# stepper-hbridge-xiao.net
KiCad netlist of a schematic drawn in EAGLE
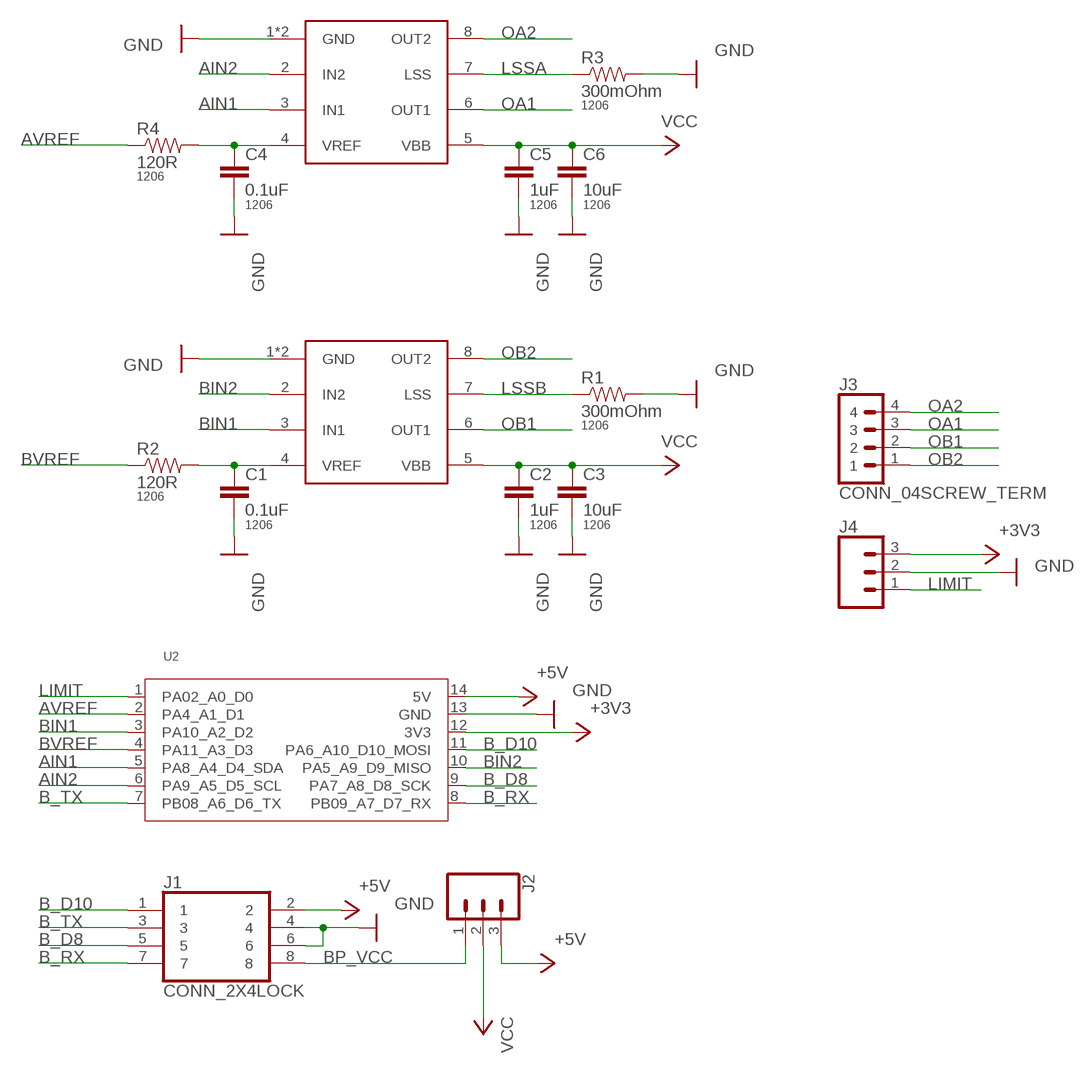
[diagram p0: schematic, sheet 1]

(export (version "E")
  (design (tool "Eeschema 10.0.6"))
  (components
    (comp (ref "C1")
      (value "0.1uF")
      (footprint "eagle-import:1206")
      (fields (field (name "PACKAGE") "1206"))
      (libsource (lib "eagle-import") (part "CAP1206"))
    )
    (comp (ref "C2")
      (value "1uF")
      (footprint "eagle-import:1206")
      (fields (field (name "PACKAGE") "1206"))
      (libsource (lib "eagle-import") (part "CAP1206"))
    )
    (comp (ref "C3")
      (value "10uF")
      (footprint "eagle-import:1206")
      (fields (field (name "PACKAGE") "1206"))
      (libsource (lib "eagle-import") (part "CAP1206"))
    )
    (comp (ref "C4")
      (value "0.1uF")
      (footprint "eagle-import:1206")
      (fields (field (name "PACKAGE") "1206"))
      (libsource (lib "eagle-import") (part "CAP1206"))
    )
    (comp (ref "C5")
      (value "1uF")
      (footprint "eagle-import:1206")
      (fields (field (name "PACKAGE") "1206"))
      (libsource (lib "eagle-import") (part "CAP1206"))
    )
    (comp (ref "C6")
      (value "10uF")
      (footprint "eagle-import:1206")
      (fields (field (name "PACKAGE") "1206"))
      (libsource (lib "eagle-import") (part "CAP1206"))
    )
    (comp (ref "J1")
      (value "CONN_2X4LOCK")
      (footprint "eagle-import:2X4-LOCK")
      (libsource (lib "eagle-import") (part "CONN_2X4LOCK"))
    )
    (comp (ref "J2")
      (value "CONN_03LOCK_NO_SILK")
      (footprint "eagle-import:1X03_LOCK_NO_SILK")
      (libsource (lib "eagle-import") (part "CONN_03LOCK_NO_SILK"))
    )
    (comp (ref "J3")
      (value "CONN_04SCREW_TERM")
      (footprint "eagle-import:1X04_SCREW-TERM")
      (libsource (lib "eagle-import") (part "CONN_04SCREW_TERM"))
    )
    (comp (ref "J4")
      (value "CONN_03LOCK_NO_SILK")
      (footprint "eagle-import:1X03_LOCK_NO_SILK")
      (libsource (lib "eagle-import") (part "CONN_03LOCK_NO_SILK"))
    )
    (comp (ref "R1")
      (value "300mOhm")
      (footprint "eagle-import:1206")
      (fields (field (name "PACKAGE") "1206"))
      (libsource (lib "eagle-import") (part "RESISTOR1206"))
    )
    (comp (ref "R2")
      (value "120R")
      (footprint "eagle-import:1206")
      (fields (field (name "PACKAGE") "1206"))
      (libsource (lib "eagle-import") (part "RESISTOR1206"))
    )
    (comp (ref "R3")
      (value "300mOhm")
      (footprint "eagle-import:1206")
      (fields (field (name "PACKAGE") "1206"))
      (libsource (lib "eagle-import") (part "RESISTOR1206"))
    )
    (comp (ref "R4")
      (value "120R")
      (footprint "eagle-import:1206")
      (fields (field (name "PACKAGE") "1206"))
      (libsource (lib "eagle-import") (part "RESISTOR1206"))
    )
    (comp (ref "U1")
      (value "A4950")
      (footprint "eagle-import:SOIC8_PAD")
      (libsource (lib "eagle-import") (part "A4950"))
    )
    (comp (ref "U2")
      (value "MOUDLE-SEEEDUINO-XIAO-DIP")
      (footprint "eagle-import:MOUDLE14P-2.54-21X17.8MM")
      (libsource (lib "eagle-import") (part "MOUDLE-SEEEDUINO-XIAO-DIP"))
    )
    (comp (ref "U3")
      (value "A4950")
      (footprint "eagle-import:SOIC8_PAD")
      (libsource (lib "eagle-import") (part "A4950"))
    )
  )
  (nets
    (net (code "1") (name "+3V3") (class "Default")
      (node (ref "J4") (pin "3") (pinfunction "3_3") (pintype "passive"))
      (node (ref "U2") (pin "12") (pinfunction "3V3_12") (pintype "bidirectional"))
    )
    (net (code "2") (name "+5V") (class "Default")
      (node (ref "J1") (pin "2") (pinfunction "2_2") (pintype "passive"))
      (node (ref "J2") (pin "3") (pinfunction "3_3") (pintype "passive"))
      (node (ref "U2") (pin "14") (pinfunction "5V_14") (pintype "bidirectional"))
    )
    (net (code "3") (name "/AIN1") (class "Default")
      (node (ref "U2") (pin "5") (pinfunction "PA8_A4_D4_SDA_5") (pintype "bidirectional"))
      (node (ref "U3") (pin "3") (pinfunction "IN1_3") (pintype "bidirectional"))
    )
    (net (code "4") (name "/AIN2") (class "Default")
      (node (ref "U2") (pin "6") (pinfunction "PA9_A5_D5_SCL_6") (pintype "bidirectional"))
      (node (ref "U3") (pin "2") (pinfunction "IN2_2") (pintype "bidirectional"))
    )
    (net (code "5") (name "/AVREF") (class "Default")
      (node (ref "R4") (pin "1") (pinfunction "1_1") (pintype "passive"))
      (node (ref "U2") (pin "2") (pinfunction "PA4_A1_D1_2") (pintype "bidirectional"))
    )
    (net (code "6") (name "/BIN1") (class "Default")
      (node (ref "U1") (pin "3") (pinfunction "IN1_3") (pintype "bidirectional"))
      (node (ref "U2") (pin "3") (pinfunction "PA10_A2_D2_3") (pintype "bidirectional"))
    )
    (net (code "7") (name "/BIN2") (class "Default")
      (node (ref "U1") (pin "2") (pinfunction "IN2_2") (pintype "bidirectional"))
      (node (ref "U2") (pin "10") (pinfunction "PA5_A9_D9_MISO_10") (pintype "bidirectional"))
    )
    (net (code "8") (name "/BP_VCC") (class "Default")
      (node (ref "J1") (pin "8") (pinfunction "8_8") (pintype "passive"))
      (node (ref "J2") (pin "1") (pinfunction "1_1") (pintype "passive"))
    )
    (net (code "9") (name "/BVREF") (class "Default")
      (node (ref "R2") (pin "1") (pinfunction "1_1") (pintype "passive"))
      (node (ref "U2") (pin "4") (pinfunction "PA11_A3_D3_4") (pintype "bidirectional"))
    )
    (net (code "10") (name "/B_D8") (class "Default")
      (node (ref "J1") (pin "5") (pinfunction "5_5") (pintype "passive"))
      (node (ref "U2") (pin "9") (pinfunction "PA7_A8_D8_SCK_9") (pintype "bidirectional"))
    )
    (net (code "11") (name "/B_D10") (class "Default")
      (node (ref "J1") (pin "1") (pinfunction "1_1") (pintype "passive"))
      (node (ref "U2") (pin "11") (pinfunction "PA6_A10_D10_MOSI_11") (pintype "bidirectional"))
    )
    (net (code "12") (name "/B_RX") (class "Default")
      (node (ref "J1") (pin "7") (pinfunction "7_7") (pintype "passive"))
      (node (ref "U2") (pin "8") (pinfunction "PB09_A7_D7_RX_8") (pintype "bidirectional"))
    )
    (net (code "13") (name "/B_TX") (class "Default")
      (node (ref "J1") (pin "3") (pinfunction "3_3") (pintype "passive"))
      (node (ref "U2") (pin "7") (pinfunction "PB08_A6_D6_TX_7") (pintype "bidirectional"))
    )
    (net (code "14") (name "/LIMIT") (class "Default")
      (node (ref "J4") (pin "1") (pinfunction "1_1") (pintype "passive"))
      (node (ref "U2") (pin "1") (pinfunction "PA02_A0_D0_1") (pintype "bidirectional"))
    )
    (net (code "15") (name "/LSSA") (class "Default")
      (node (ref "R3") (pin "1") (pinfunction "1_1") (pintype "passive"))
      (node (ref "U3") (pin "7") (pinfunction "LSS_7") (pintype "bidirectional"))
    )
    (net (code "16") (name "/LSSB") (class "Default")
      (node (ref "R1") (pin "1") (pinfunction "1_1") (pintype "passive"))
      (node (ref "U1") (pin "7") (pinfunction "LSS_7") (pintype "bidirectional"))
    )
    (net (code "17") (name "/OA1") (class "Default")
      (node (ref "J3") (pin "3") (pinfunction "3_3") (pintype "passive"))
      (node (ref "U3") (pin "6") (pinfunction "OUT1_6") (pintype "bidirectional"))
    )
    (net (code "18") (name "/OA2") (class "Default")
      (node (ref "J3") (pin "4") (pinfunction "4_4") (pintype "passive"))
      (node (ref "U3") (pin "8") (pinfunction "OUT2_8") (pintype "bidirectional"))
    )
    (net (code "19") (name "/OB1") (class "Default")
      (node (ref "J3") (pin "2") (pinfunction "2_2") (pintype "passive"))
      (node (ref "U1") (pin "6") (pinfunction "OUT1_6") (pintype "bidirectional"))
    )
    (net (code "20") (name "/OB2") (class "Default")
      (node (ref "J3") (pin "1") (pinfunction "1_1") (pintype "passive"))
      (node (ref "U1") (pin "8") (pinfunction "OUT2_8") (pintype "bidirectional"))
    )
    (net (code "21") (name "GND") (class "Default")
      (node (ref "C1") (pin "2") (pinfunction "2_2") (pintype "passive"))
      (node (ref "C2") (pin "2") (pinfunction "2_2") (pintype "passive"))
      (node (ref "C3") (pin "2") (pinfunction "2_2") (pintype "passive"))
      (node (ref "C4") (pin "2") (pinfunction "2_2") (pintype "passive"))
      (node (ref "C5") (pin "2") (pinfunction "2_2") (pintype "passive"))
      (node (ref "C6") (pin "2") (pinfunction "2_2") (pintype "passive"))
      (node (ref "J1") (pin "4") (pinfunction "4_4") (pintype "passive"))
      (node (ref "J1") (pin "6") (pinfunction "6_6") (pintype "passive"))
      (node (ref "J4") (pin "2") (pinfunction "2_2") (pintype "passive"))
      (node (ref "R1") (pin "2") (pinfunction "2_2") (pintype "passive"))
      (node (ref "R3") (pin "2") (pinfunction "2_2") (pintype "passive"))
      (node (ref "U1") (pin "1") (pinfunction "GND_1") (pintype "bidirectional"))
      (node (ref "U1") (pin "P$1") (pinfunction "GND_P$1") (pintype "bidirectional"))
      (node (ref "U2") (pin "13") (pinfunction "GND_13") (pintype "bidirectional"))
      (node (ref "U3") (pin "1") (pinfunction "GND_1") (pintype "bidirectional"))
      (node (ref "U3") (pin "P$1") (pinfunction "GND_P$1") (pintype "bidirectional"))
    )
    (net (code "22") (name "Net-(U1-VREF)") (class "Default")
      (node (ref "C1") (pin "1") (pinfunction "1_1") (pintype "passive"))
      (node (ref "R2") (pin "2") (pinfunction "2_2") (pintype "passive"))
      (node (ref "U1") (pin "4") (pinfunction "VREF_4") (pintype "bidirectional"))
    )
    (net (code "23") (name "Net-(U3-VREF)") (class "Default")
      (node (ref "C4") (pin "1") (pinfunction "1_1") (pintype "passive"))
      (node (ref "R4") (pin "2") (pinfunction "2_2") (pintype "passive"))
      (node (ref "U3") (pin "4") (pinfunction "VREF_4") (pintype "bidirectional"))
    )
    (net (code "24") (name "VCC") (class "Default")
      (node (ref "C2") (pin "1") (pinfunction "1_1") (pintype "passive"))
      (node (ref "C3") (pin "1") (pinfunction "1_1") (pintype "passive"))
      (node (ref "C5") (pin "1") (pinfunction "1_1") (pintype "passive"))
      (node (ref "C6") (pin "1") (pinfunction "1_1") (pintype "passive"))
      (node (ref "J2") (pin "2") (pinfunction "2_2") (pintype "passive"))
      (node (ref "U1") (pin "5") (pinfunction "VBB_5") (pintype "bidirectional"))
      (node (ref "U3") (pin "5") (pinfunction "VBB_5") (pintype "bidirectional"))
    )
  )
)
